# C128_Keyb_Test.net
KiCad netlist of a schematic drawn in EAGLE
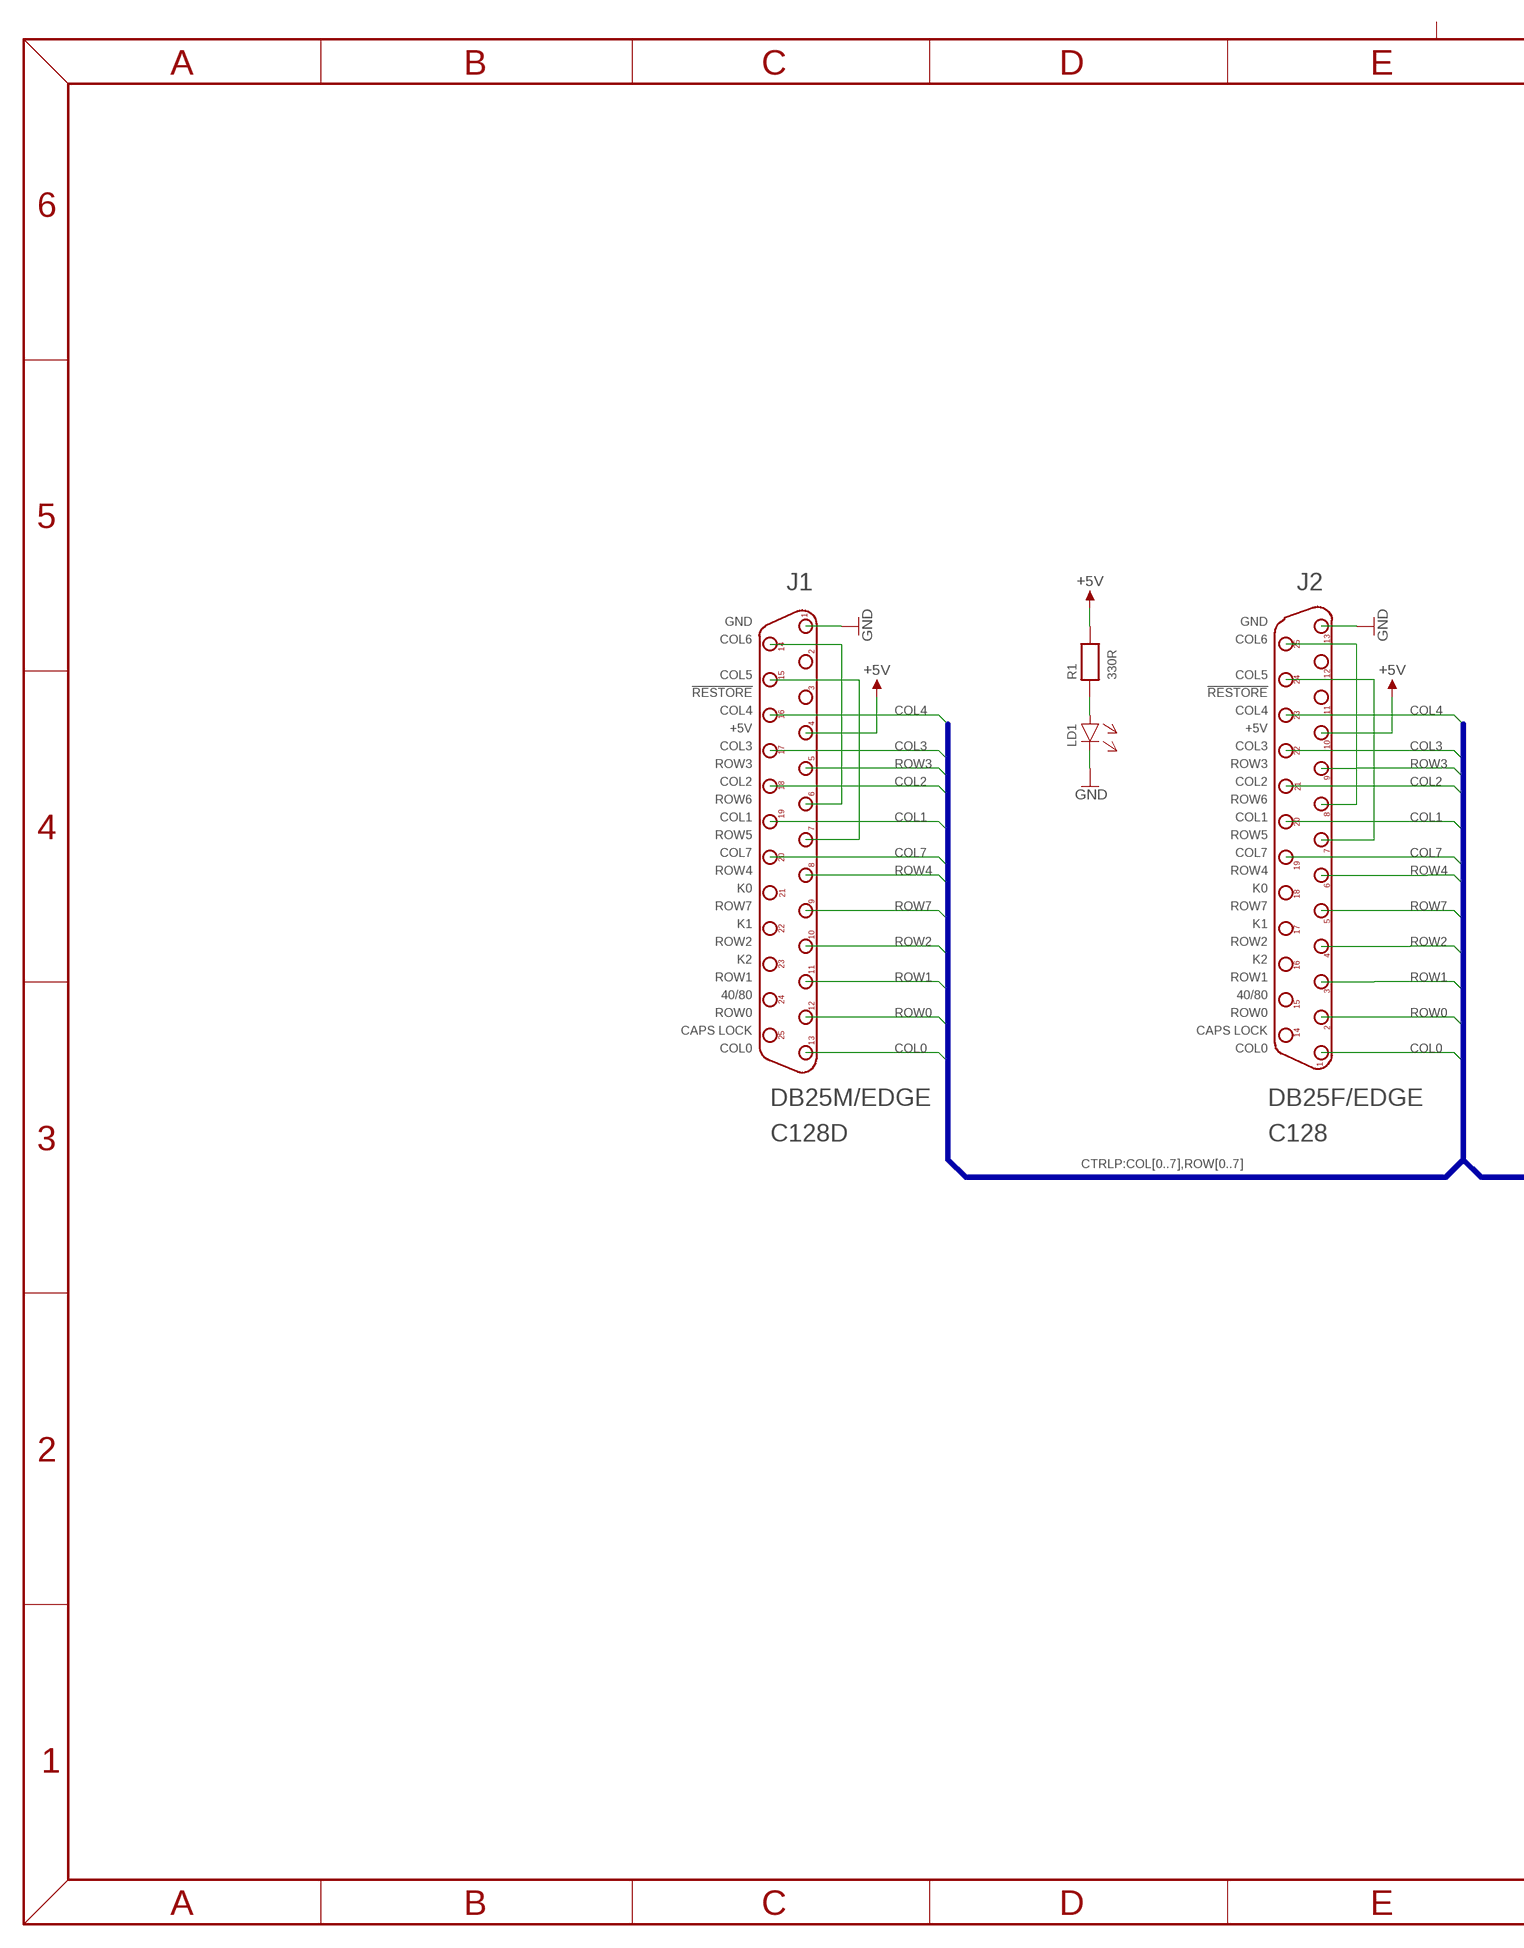
[diagram p0: schematic, sheet 1, part 1 of 2]
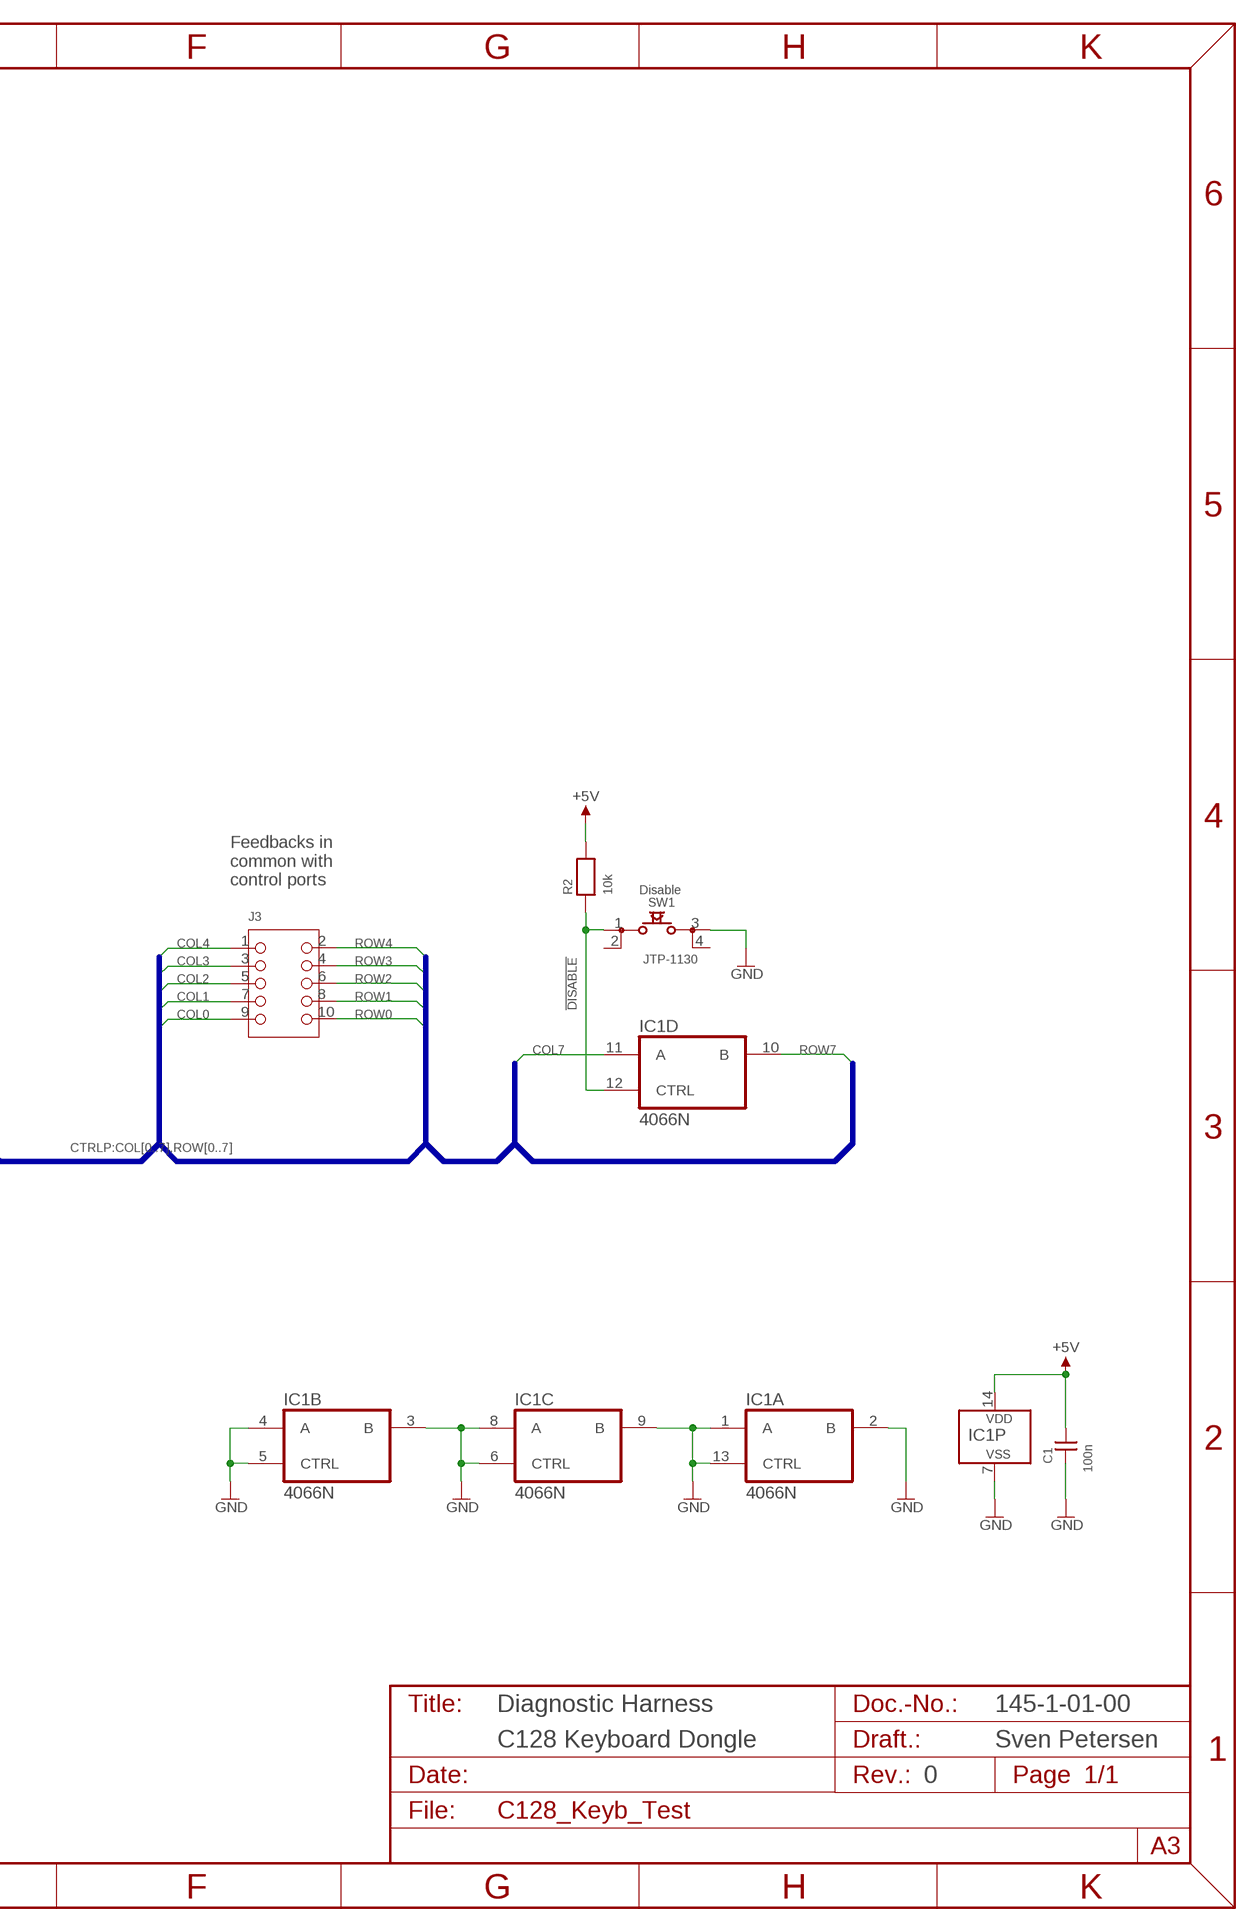
[diagram p1: schematic, sheet 1, part 2 of 2]

(export (version "E")
  (design (tool "Eeschema 10.0.6"))
  (components
    (comp (ref "C1")
      (value "100n")
      (footprint "eagle-import:C-2,5")
      (libsource (lib "eagle-import") (part "CAP01"))
    )
    (comp (ref "IC1")
      (value "4066N")
      (footprint "eagle-import:DIL14")
      (libsource (lib "eagle-import") (part "4066N"))
    )
    (comp (ref "J1")
      (value "DB25M/EDGE")
      (footprint "eagle-import:DB25M-EDGE")
      (libsource (lib "eagle-import") (part "DB25M/EDGE"))
    )
    (comp (ref "J2")
      (value "DB25F/EDGE")
      (footprint "eagle-import:DB25F-EDGE")
      (libsource (lib "eagle-import") (part "DB25F/EDGE"))
    )
    (comp (ref "J3")
      (value "2X05WV")
      (footprint "eagle-import:2X05WV")
      (libsource (lib "eagle-import") (part "2X05WV"))
    )
    (comp (ref "LD1")
      (value "3MM")
      (footprint "eagle-import:3MM")
      (libsource (lib "eagle-import") (part "3MM"))
    )
    (comp (ref "R1")
      (value "330R")
      (footprint "eagle-import:R-10")
      (libsource (lib "eagle-import") (part "RES04"))
    )
    (comp (ref "R2")
      (value "10k")
      (footprint "eagle-import:R-10")
      (libsource (lib "eagle-import") (part "RES04"))
    )
    (comp (ref "SW1")
      (value "JTP-1130")
      (footprint "eagle-import:JTP-1130")
      (libsource (lib "eagle-import") (part "JTP-1130"))
    )
  )
  (nets
    (net (code "1") (name "+5V") (class "Default")
      (node (ref "C1") (pin "2") (pinfunction "2_2") (pintype "passive"))
      (node (ref "IC1") (pin "14") (pinfunction "VDD_14") (pintype "power_in"))
      (node (ref "J1") (pin "4") (pinfunction "4_4") (pintype "passive"))
      (node (ref "J2") (pin "10") (pinfunction "10_10") (pintype "passive"))
      (node (ref "R1") (pin "2") (pinfunction "2_2") (pintype "passive"))
      (node (ref "R2") (pin "2") (pinfunction "2_2") (pintype "passive"))
    )
    (net (code "2") (name "/COL0") (class "Default")
      (node (ref "J1") (pin "13") (pinfunction "13_13") (pintype "passive"))
      (node (ref "J2") (pin "1") (pinfunction "1_1") (pintype "passive"))
      (node (ref "J3") (pin "9") (pinfunction "9_9") (pintype "passive"))
    )
    (net (code "3") (name "/COL1") (class "Default")
      (node (ref "J1") (pin "19") (pinfunction "19_19") (pintype "passive"))
      (node (ref "J2") (pin "20") (pinfunction "20_20") (pintype "passive"))
      (node (ref "J3") (pin "7") (pinfunction "7_7") (pintype "passive"))
    )
    (net (code "4") (name "/COL2") (class "Default")
      (node (ref "J1") (pin "18") (pinfunction "18_18") (pintype "passive"))
      (node (ref "J2") (pin "21") (pinfunction "21_21") (pintype "passive"))
      (node (ref "J3") (pin "5") (pinfunction "5_5") (pintype "passive"))
    )
    (net (code "5") (name "/COL3") (class "Default")
      (node (ref "J1") (pin "17") (pinfunction "17_17") (pintype "passive"))
      (node (ref "J2") (pin "22") (pinfunction "22_22") (pintype "passive"))
      (node (ref "J3") (pin "3") (pinfunction "3_3") (pintype "passive"))
    )
    (net (code "6") (name "/COL4") (class "Default")
      (node (ref "J1") (pin "16") (pinfunction "16_16") (pintype "passive"))
      (node (ref "J2") (pin "23") (pinfunction "23_23") (pintype "passive"))
      (node (ref "J3") (pin "1") (pinfunction "1_1") (pintype "passive"))
    )
    (net (code "7") (name "/COL7") (class "Default")
      (node (ref "IC1") (pin "11") (pinfunction "A_11") (pintype "tri_state"))
      (node (ref "J1") (pin "20") (pinfunction "20_20") (pintype "passive"))
      (node (ref "J2") (pin "19") (pinfunction "19_19") (pintype "passive"))
    )
    (net (code "8") (name "/ROW0") (class "Default")
      (node (ref "J1") (pin "12") (pinfunction "12_12") (pintype "passive"))
      (node (ref "J2") (pin "2") (pinfunction "2_2") (pintype "passive"))
      (node (ref "J3") (pin "10") (pinfunction "10_10") (pintype "passive"))
    )
    (net (code "9") (name "/ROW1") (class "Default")
      (node (ref "J1") (pin "11") (pinfunction "11_11") (pintype "passive"))
      (node (ref "J2") (pin "3") (pinfunction "3_3") (pintype "passive"))
      (node (ref "J3") (pin "8") (pinfunction "8_8") (pintype "passive"))
    )
    (net (code "10") (name "/ROW2") (class "Default")
      (node (ref "J1") (pin "10") (pinfunction "10_10") (pintype "passive"))
      (node (ref "J2") (pin "4") (pinfunction "4_4") (pintype "passive"))
      (node (ref "J3") (pin "6") (pinfunction "6_6") (pintype "passive"))
    )
    (net (code "11") (name "/ROW3") (class "Default")
      (node (ref "J1") (pin "5") (pinfunction "5_5") (pintype "passive"))
      (node (ref "J2") (pin "9") (pinfunction "9_9") (pintype "passive"))
      (node (ref "J3") (pin "4") (pinfunction "4_4") (pintype "passive"))
    )
    (net (code "12") (name "/ROW4") (class "Default")
      (node (ref "J1") (pin "8") (pinfunction "8_8") (pintype "passive"))
      (node (ref "J2") (pin "6") (pinfunction "6_6") (pintype "passive"))
      (node (ref "J3") (pin "2") (pinfunction "2_2") (pintype "passive"))
    )
    (net (code "13") (name "/ROW7") (class "Default")
      (node (ref "IC1") (pin "10") (pinfunction "B_10") (pintype "tri_state"))
      (node (ref "J1") (pin "9") (pinfunction "9_9") (pintype "passive"))
      (node (ref "J2") (pin "5") (pinfunction "5_5") (pintype "passive"))
    )
    (net (code "15") (name "/~{DISABLE}") (class "Default")
      (node (ref "IC1") (pin "12") (pinfunction "CTRL_12") (pintype "input"))
      (node (ref "R2") (pin "1") (pinfunction "1_1") (pintype "passive"))
      (node (ref "SW1") (pin "1") (pinfunction "1_1") (pintype "passive"))
    )
    (net (code "16") (name "GND") (class "Default")
      (node (ref "C1") (pin "1") (pinfunction "1_1") (pintype "passive"))
      (node (ref "IC1") (pin "1") (pinfunction "A_1") (pintype "tri_state"))
      (node (ref "IC1") (pin "13") (pinfunction "CTRL_13") (pintype "input"))
      (node (ref "IC1") (pin "2") (pinfunction "B_2") (pintype "tri_state"))
      (node (ref "IC1") (pin "3") (pinfunction "B_3") (pintype "tri_state"))
      (node (ref "IC1") (pin "4") (pinfunction "A_4") (pintype "tri_state"))
      (node (ref "IC1") (pin "5") (pinfunction "CTRL_5") (pintype "input"))
      (node (ref "IC1") (pin "6") (pinfunction "CTRL_6") (pintype "input"))
      (node (ref "IC1") (pin "7") (pinfunction "VSS_7") (pintype "power_in"))
      (node (ref "IC1") (pin "8") (pinfunction "A_8") (pintype "tri_state"))
      (node (ref "IC1") (pin "9") (pinfunction "B_9") (pintype "tri_state"))
      (node (ref "J1") (pin "1") (pinfunction "1_1") (pintype "passive"))
      (node (ref "J2") (pin "13") (pinfunction "13_13") (pintype "passive"))
      (node (ref "LD1") (pin "C") (pinfunction "K_C") (pintype "bidirectional"))
      (node (ref "SW1") (pin "3") (pinfunction "3_3") (pintype "passive"))
    )
    (net (code "17") (name "Net-(J1-Pad14)") (class "Default")
      (node (ref "J1") (pin "14") (pinfunction "14_14") (pintype "passive"))
      (node (ref "J1") (pin "6") (pinfunction "6_6") (pintype "passive"))
    )
    (net (code "18") (name "Net-(J1-Pad15)") (class "Default")
      (node (ref "J1") (pin "15") (pinfunction "15_15") (pintype "passive"))
      (node (ref "J1") (pin "7") (pinfunction "7_7") (pintype "passive"))
    )
    (net (code "19") (name "Net-(J2-Pad24)") (class "Default")
      (node (ref "J2") (pin "24") (pinfunction "24_24") (pintype "passive"))
      (node (ref "J2") (pin "7") (pinfunction "7_7") (pintype "passive"))
    )
    (net (code "20") (name "Net-(J2-Pad25)") (class "Default")
      (node (ref "J2") (pin "25") (pinfunction "25_25") (pintype "passive"))
      (node (ref "J2") (pin "8") (pinfunction "8_8") (pintype "passive"))
    )
    (net (code "21") (name "Net-(LD1-PadA)") (class "Default")
      (node (ref "LD1") (pin "A") (pinfunction "A_A") (pintype "bidirectional"))
      (node (ref "R1") (pin "1") (pinfunction "1_1") (pintype "passive"))
    )
    (net (code "22") (name "unconnected-(J1-Pad2)") (class "Default")
      (node (ref "J1") (pin "2") (pinfunction "2_2") (pintype "passive"))
    )
    (net (code "23") (name "unconnected-(J1-Pad3)") (class "Default")
      (node (ref "J1") (pin "3") (pinfunction "3_3") (pintype "passive"))
    )
    (net (code "24") (name "unconnected-(J1-Pad21)") (class "Default")
      (node (ref "J1") (pin "21") (pinfunction "21_21") (pintype "passive"))
    )
    (net (code "25") (name "unconnected-(J1-Pad22)") (class "Default")
      (node (ref "J1") (pin "22") (pinfunction "22_22") (pintype "passive"))
    )
    (net (code "26") (name "unconnected-(J1-Pad23)") (class "Default")
      (node (ref "J1") (pin "23") (pinfunction "23_23") (pintype "passive"))
    )
    (net (code "27") (name "unconnected-(J1-Pad24)") (class "Default")
      (node (ref "J1") (pin "24") (pinfunction "24_24") (pintype "passive"))
    )
    (net (code "28") (name "unconnected-(J1-Pad25)") (class "Default")
      (node (ref "J1") (pin "25") (pinfunction "25_25") (pintype "passive"))
    )
    (net (code "29") (name "unconnected-(J2-Pad11)") (class "Default")
      (node (ref "J2") (pin "11") (pinfunction "11_11") (pintype "passive"))
    )
    (net (code "30") (name "unconnected-(J2-Pad12)") (class "Default")
      (node (ref "J2") (pin "12") (pinfunction "12_12") (pintype "passive"))
    )
    (net (code "31") (name "unconnected-(J2-Pad14)") (class "Default")
      (node (ref "J2") (pin "14") (pinfunction "14_14") (pintype "passive"))
    )
    (net (code "32") (name "unconnected-(J2-Pad15)") (class "Default")
      (node (ref "J2") (pin "15") (pinfunction "15_15") (pintype "passive"))
    )
    (net (code "33") (name "unconnected-(J2-Pad16)") (class "Default")
      (node (ref "J2") (pin "16") (pinfunction "16_16") (pintype "passive"))
    )
    (net (code "34") (name "unconnected-(J2-Pad17)") (class "Default")
      (node (ref "J2") (pin "17") (pinfunction "17_17") (pintype "passive"))
    )
    (net (code "35") (name "unconnected-(J2-Pad18)") (class "Default")
      (node (ref "J2") (pin "18") (pinfunction "18_18") (pintype "passive"))
    )
    (net (code "36") (name "unconnected-(SW1-Pad2)") (class "Default")
      (node (ref "SW1") (pin "2") (pinfunction "2_2") (pintype "passive"))
    )
    (net (code "37") (name "unconnected-(SW1-Pad4)") (class "Default")
      (node (ref "SW1") (pin "4") (pinfunction "4_4") (pintype "passive"))
    )
  )
)
